# Robot_Psoc.net
KiCad netlist of a schematic drawn in EAGLE
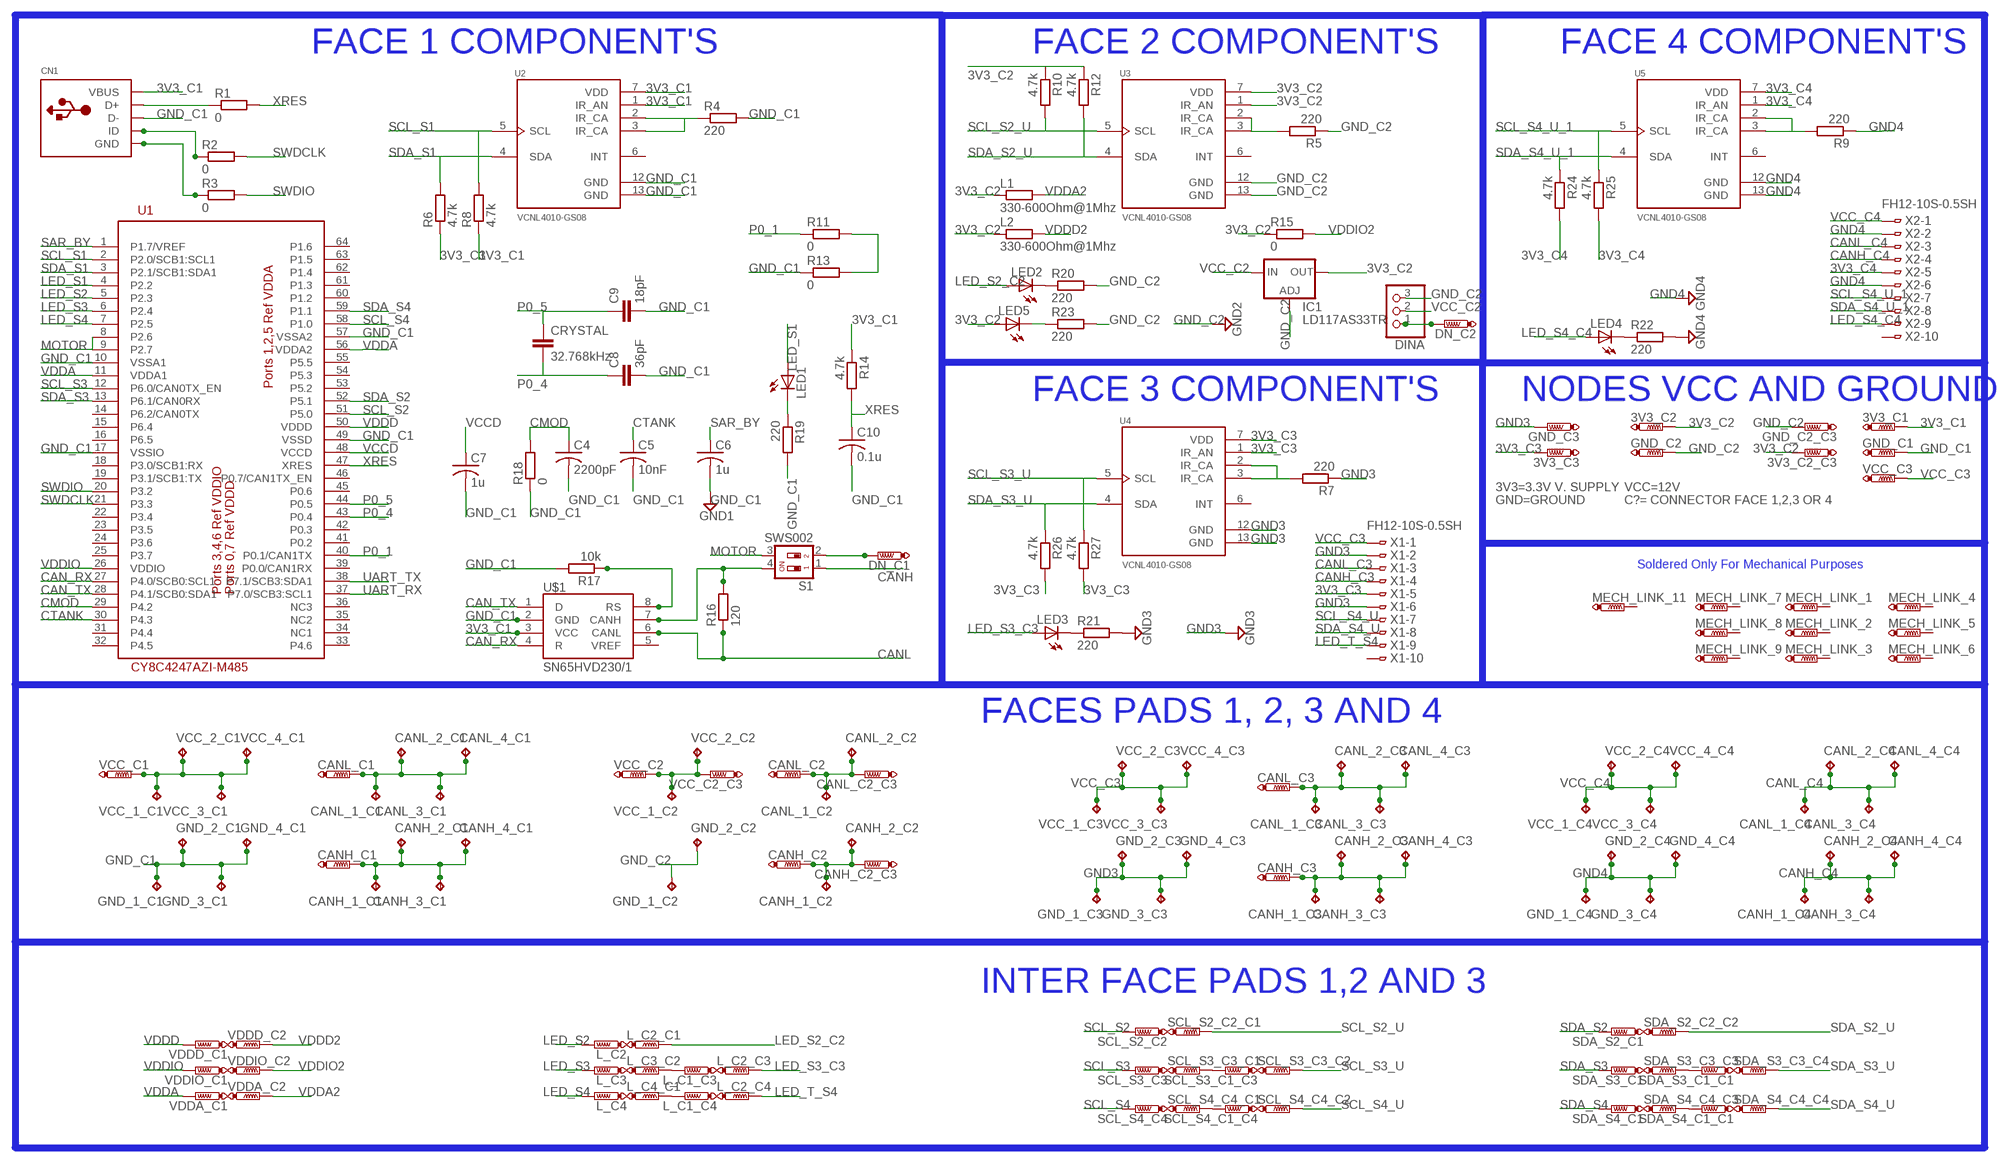
[diagram p0: schematic, sheet 1]

(export (version "E")
  (design (tool "Eeschema 10.0.6"))
  (components
    (comp (ref "3V3_C1")
      (value "PTR1TP11R")
      (footprint "eagle-import:TP11R")
      (libsource (lib "eagle-import") (part "PTR1TP11R"))
    )
    (comp (ref "3V3_C2")
      (value "PTR1TP11R")
      (footprint "eagle-import:TP11R")
      (libsource (lib "eagle-import") (part "PTR1TP11R"))
    )
    (comp (ref "3V3_C2_C3")
      (value "PTR1TP11R")
      (footprint "eagle-import:TP11R")
      (libsource (lib "eagle-import") (part "PTR1TP11R"))
    )
    (comp (ref "3V3_C3")
      (value "PTR1TP11R")
      (footprint "eagle-import:TP11R")
      (libsource (lib "eagle-import") (part "PTR1TP11R"))
    )
    (comp (ref "C4")
      (value "2200pF")
      (footprint "eagle-import:C0805")
      (libsource (lib "eagle-import") (part "C-USC0805"))
    )
    (comp (ref "C5")
      (value "10nF")
      (footprint "eagle-import:C0805")
      (libsource (lib "eagle-import") (part "C-USC0805"))
    )
    (comp (ref "C6")
      (value "1u")
      (footprint "eagle-import:C0805")
      (libsource (lib "eagle-import") (part "C-USC0805"))
    )
    (comp (ref "C7")
      (value "1u")
      (footprint "eagle-import:C0805")
      (libsource (lib "eagle-import") (part "C-USC0805"))
    )
    (comp (ref "C8")
      (value "36pF")
      (footprint "eagle-import:C0805")
      (libsource (lib "eagle-import") (part "C-EUC0805"))
    )
    (comp (ref "C9")
      (value "18pF")
      (footprint "eagle-import:C0805")
      (libsource (lib "eagle-import") (part "C-EUC0805"))
    )
    (comp (ref "C10")
      (value "0.1u")
      (footprint "eagle-import:C0805")
      (libsource (lib "eagle-import") (part "C-USC0805"))
    )
    (comp (ref "CANH_1_C1")
      (value "TPB2,54")
      (footprint "eagle-import:B2,54")
      (libsource (lib "eagle-import") (part "TPB2,54"))
    )
    (comp (ref "CANH_1_C2")
      (value "TPB2,54")
      (footprint "eagle-import:B2,54")
      (libsource (lib "eagle-import") (part "TPB2,54"))
    )
    (comp (ref "CANH_1_C3")
      (value "TPB2,54")
      (footprint "eagle-import:B2,54")
      (libsource (lib "eagle-import") (part "TPB2,54"))
    )
    (comp (ref "CANH_1_C4")
      (value "TPB2,54")
      (footprint "eagle-import:B2,54")
      (libsource (lib "eagle-import") (part "TPB2,54"))
    )
    (comp (ref "CANH_2_C1")
      (value "TPB2,54")
      (footprint "eagle-import:B2,54")
      (libsource (lib "eagle-import") (part "TPB2,54"))
    )
    (comp (ref "CANH_2_C2")
      (value "TPB2,54")
      (footprint "eagle-import:B2,54")
      (libsource (lib "eagle-import") (part "TPB2,54"))
    )
    (comp (ref "CANH_2_C3")
      (value "TPB2,54")
      (footprint "eagle-import:B2,54")
      (libsource (lib "eagle-import") (part "TPB2,54"))
    )
    (comp (ref "CANH_2_C4")
      (value "TPB2,54")
      (footprint "eagle-import:B2,54")
      (libsource (lib "eagle-import") (part "TPB2,54"))
    )
    (comp (ref "CANH_3_C1")
      (value "TPB2,54")
      (footprint "eagle-import:B2,54")
      (libsource (lib "eagle-import") (part "TPB2,54"))
    )
    (comp (ref "CANH_3_C3")
      (value "TPB2,54")
      (footprint "eagle-import:B2,54")
      (libsource (lib "eagle-import") (part "TPB2,54"))
    )
    (comp (ref "CANH_3_C4")
      (value "TPB2,54")
      (footprint "eagle-import:B2,54")
      (libsource (lib "eagle-import") (part "TPB2,54"))
    )
    (comp (ref "CANH_4_C1")
      (value "TPB2,54")
      (footprint "eagle-import:B2,54")
      (libsource (lib "eagle-import") (part "TPB2,54"))
    )
    (comp (ref "CANH_4_C3")
      (value "TPB2,54")
      (footprint "eagle-import:B2,54")
      (libsource (lib "eagle-import") (part "TPB2,54"))
    )
    (comp (ref "CANH_4_C4")
      (value "TPB2,54")
      (footprint "eagle-import:B2,54")
      (libsource (lib "eagle-import") (part "TPB2,54"))
    )
    (comp (ref "CANH_C1")
      (value "PTR1TP11R")
      (footprint "eagle-import:TP11R")
      (libsource (lib "eagle-import") (part "PTR1TP11R"))
    )
    (comp (ref "CANH_C2")
      (value "PTR1TP11R")
      (footprint "eagle-import:TP11R")
      (libsource (lib "eagle-import") (part "PTR1TP11R"))
    )
    (comp (ref "CANH_C2_C3")
      (value "PTR1TP11R")
      (footprint "eagle-import:TP11R")
      (libsource (lib "eagle-import") (part "PTR1TP11R"))
    )
    (comp (ref "CANH_C3")
      (value "PTR1TP11R")
      (footprint "eagle-import:TP11R")
      (libsource (lib "eagle-import") (part "PTR1TP11R"))
    )
    (comp (ref "CANL_1_C1")
      (value "TPB2,54")
      (footprint "eagle-import:B2,54")
      (libsource (lib "eagle-import") (part "TPB2,54"))
    )
    (comp (ref "CANL_1_C2")
      (value "TPB2,54")
      (footprint "eagle-import:B2,54")
      (libsource (lib "eagle-import") (part "TPB2,54"))
    )
    (comp (ref "CANL_1_C3")
      (value "TPB2,54")
      (footprint "eagle-import:B2,54")
      (libsource (lib "eagle-import") (part "TPB2,54"))
    )
    (comp (ref "CANL_1_C4")
      (value "TPB2,54")
      (footprint "eagle-import:B2,54")
      (libsource (lib "eagle-import") (part "TPB2,54"))
    )
    (comp (ref "CANL_2_C1")
      (value "TPB2,54")
      (footprint "eagle-import:B2,54")
      (libsource (lib "eagle-import") (part "TPB2,54"))
    )
    (comp (ref "CANL_2_C2")
      (value "TPB2,54")
      (footprint "eagle-import:B2,54")
      (libsource (lib "eagle-import") (part "TPB2,54"))
    )
    (comp (ref "CANL_2_C3")
      (value "TPB2,54")
      (footprint "eagle-import:B2,54")
      (libsource (lib "eagle-import") (part "TPB2,54"))
    )
    (comp (ref "CANL_2_C4")
      (value "TPB2,54")
      (footprint "eagle-import:B2,54")
      (libsource (lib "eagle-import") (part "TPB2,54"))
    )
    (comp (ref "CANL_3_C1")
      (value "TPB2,54")
      (footprint "eagle-import:B2,54")
      (libsource (lib "eagle-import") (part "TPB2,54"))
    )
    (comp (ref "CANL_3_C3")
      (value "TPB2,54")
      (footprint "eagle-import:B2,54")
      (libsource (lib "eagle-import") (part "TPB2,54"))
    )
    (comp (ref "CANL_3_C4")
      (value "TPB2,54")
      (footprint "eagle-import:B2,54")
      (libsource (lib "eagle-import") (part "TPB2,54"))
    )
    (comp (ref "CANL_4_C1")
      (value "TPB2,54")
      (footprint "eagle-import:B2,54")
      (libsource (lib "eagle-import") (part "TPB2,54"))
    )
    (comp (ref "CANL_4_C3")
      (value "TPB2,54")
      (footprint "eagle-import:B2,54")
      (libsource (lib "eagle-import") (part "TPB2,54"))
    )
    (comp (ref "CANL_4_C4")
      (value "TPB2,54")
      (footprint "eagle-import:B2,54")
      (libsource (lib "eagle-import") (part "TPB2,54"))
    )
    (comp (ref "CANL_C1")
      (value "PTR1TP11R")
      (footprint "eagle-import:TP11R")
      (libsource (lib "eagle-import") (part "PTR1TP11R"))
    )
    (comp (ref "CANL_C2")
      (value "PTR1TP11R")
      (footprint "eagle-import:TP11R")
      (libsource (lib "eagle-import") (part "PTR1TP11R"))
    )
    (comp (ref "CANL_C2_C3")
      (value "PTR1TP11R")
      (footprint "eagle-import:TP11R")
      (libsource (lib "eagle-import") (part "PTR1TP11R"))
    )
    (comp (ref "CANL_C3")
      (value "PTR1TP11R")
      (footprint "eagle-import:TP11R")
      (libsource (lib "eagle-import") (part "PTR1TP11R"))
    )
    (comp (ref "CN1")
      (value "USBMINIB")
      (footprint "eagle-import:USB-MINIB")
      (libsource (lib "eagle-import") (part "USBMINIB"))
    )
    (comp (ref "CRYSTAL")
      (value "32.768kHz")
      (footprint "eagle-import:C0603")
      (libsource (lib "eagle-import") (part "C-EUC0603"))
    )
    (comp (ref "DINA")
      (value "PINHD-1X3")
      (footprint "eagle-import:1X03")
      (libsource (lib "eagle-import") (part "PINHD-1X3"))
    )
    (comp (ref "DN_C1")
      (value "PTR1TP11R")
      (footprint "eagle-import:TP11R")
      (libsource (lib "eagle-import") (part "PTR1TP11R"))
    )
    (comp (ref "DN_C2")
      (value "PTR1TP11R")
      (footprint "eagle-import:TP11R")
      (libsource (lib "eagle-import") (part "PTR1TP11R"))
    )
    (comp (ref "GND_1_C1")
      (value "TPB2,54")
      (footprint "eagle-import:B2,54")
      (libsource (lib "eagle-import") (part "TPB2,54"))
    )
    (comp (ref "GND_1_C2")
      (value "TPB2,54")
      (footprint "eagle-import:B2,54")
      (libsource (lib "eagle-import") (part "TPB2,54"))
    )
    (comp (ref "GND_1_C3")
      (value "TPB2,54")
      (footprint "eagle-import:B2,54")
      (libsource (lib "eagle-import") (part "TPB2,54"))
    )
    (comp (ref "GND_1_C4")
      (value "TPB2,54")
      (footprint "eagle-import:B2,54")
      (libsource (lib "eagle-import") (part "TPB2,54"))
    )
    (comp (ref "GND_2_C1")
      (value "TPB2,54")
      (footprint "eagle-import:B2,54")
      (libsource (lib "eagle-import") (part "TPB2,54"))
    )
    (comp (ref "GND_2_C2")
      (value "TPB2,54")
      (footprint "eagle-import:B2,54")
      (libsource (lib "eagle-import") (part "TPB2,54"))
    )
    (comp (ref "GND_2_C3")
      (value "TPB2,54")
      (footprint "eagle-import:B2,54")
      (libsource (lib "eagle-import") (part "TPB2,54"))
    )
    (comp (ref "GND_2_C4")
      (value "TPB2,54")
      (footprint "eagle-import:B2,54")
      (libsource (lib "eagle-import") (part "TPB2,54"))
    )
    (comp (ref "GND_3_C1")
      (value "TPB2,54")
      (footprint "eagle-import:B2,54")
      (libsource (lib "eagle-import") (part "TPB2,54"))
    )
    (comp (ref "GND_3_C3")
      (value "TPB2,54")
      (footprint "eagle-import:B2,54")
      (libsource (lib "eagle-import") (part "TPB2,54"))
    )
    (comp (ref "GND_3_C4")
      (value "TPB2,54")
      (footprint "eagle-import:B2,54")
      (libsource (lib "eagle-import") (part "TPB2,54"))
    )
    (comp (ref "GND_4_C1")
      (value "TPB2,54")
      (footprint "eagle-import:B2,54")
      (libsource (lib "eagle-import") (part "TPB2,54"))
    )
    (comp (ref "GND_4_C3")
      (value "TPB2,54")
      (footprint "eagle-import:B2,54")
      (libsource (lib "eagle-import") (part "TPB2,54"))
    )
    (comp (ref "GND_4_C4")
      (value "TPB2,54")
      (footprint "eagle-import:B2,54")
      (libsource (lib "eagle-import") (part "TPB2,54"))
    )
    (comp (ref "GND_C1")
      (value "PTR1TP11R")
      (footprint "eagle-import:TP11R")
      (libsource (lib "eagle-import") (part "PTR1TP11R"))
    )
    (comp (ref "GND_C2")
      (value "PTR1TP11R")
      (footprint "eagle-import:TP11R")
      (libsource (lib "eagle-import") (part "PTR1TP11R"))
    )
    (comp (ref "GND_C2_C3")
      (value "PTR1TP11R")
      (footprint "eagle-import:TP11R")
      (libsource (lib "eagle-import") (part "PTR1TP11R"))
    )
    (comp (ref "GND_C3")
      (value "PTR1TP11R")
      (footprint "eagle-import:TP11R")
      (libsource (lib "eagle-import") (part "PTR1TP11R"))
    )
    (comp (ref "IC1")
      (value "LD117AS33TR")
      (footprint "eagle-import:SOT223")
      (libsource (lib "eagle-import") (part "LD117A?S33TR"))
    )
    (comp (ref "L1")
      (value "330-600Ohm@1Mhz")
      (footprint "eagle-import:R0805")
      (libsource (lib "eagle-import") (part "R-EU_R0805"))
    )
    (comp (ref "L2")
      (value "330-600Ohm@1Mhz")
      (footprint "eagle-import:R0805")
      (libsource (lib "eagle-import") (part "R-EU_R0805"))
    )
    (comp (ref "LED1")
      (value "LEDCHIPLED_0805")
      (footprint "eagle-import:CHIPLED_0805")
      (libsource (lib "eagle-import") (part "LEDCHIPLED_0805"))
    )
    (comp (ref "LED2")
      (value "LEDCHIPLED_0805")
      (footprint "eagle-import:CHIPLED_0805")
      (libsource (lib "eagle-import") (part "LEDCHIPLED_0805"))
    )
    (comp (ref "LED3")
      (value "LEDCHIPLED_0805")
      (footprint "eagle-import:CHIPLED_0805")
      (libsource (lib "eagle-import") (part "LEDCHIPLED_0805"))
    )
    (comp (ref "LED4")
      (value "LEDCHIPLED_0805")
      (footprint "eagle-import:CHIPLED_0805")
      (libsource (lib "eagle-import") (part "LEDCHIPLED_0805"))
    )
    (comp (ref "LED5")
      (value "LEDCHIPLED_0805")
      (footprint "eagle-import:CHIPLED_0805")
      (libsource (lib "eagle-import") (part "LEDCHIPLED_0805"))
    )
    (comp (ref "L_C1_C3")
      (value "PTR1TP11R")
      (footprint "eagle-import:TP11R")
      (libsource (lib "eagle-import") (part "PTR1TP11R"))
    )
    (comp (ref "L_C1_C4")
      (value "PTR1TP11R")
      (footprint "eagle-import:TP11R")
      (libsource (lib "eagle-import") (part "PTR1TP11R"))
    )
    (comp (ref "L_C2")
      (value "PTR1TP11R")
      (footprint "eagle-import:TP11R")
      (libsource (lib "eagle-import") (part "PTR1TP11R"))
    )
    (comp (ref "L_C2_C1")
      (value "PTR1TP11R")
      (footprint "eagle-import:TP11R")
      (libsource (lib "eagle-import") (part "PTR1TP11R"))
    )
    (comp (ref "L_C2_C3")
      (value "PTR1TP11R")
      (footprint "eagle-import:TP11R")
      (libsource (lib "eagle-import") (part "PTR1TP11R"))
    )
    (comp (ref "L_C2_C4")
      (value "PTR1TP11R")
      (footprint "eagle-import:TP11R")
      (libsource (lib "eagle-import") (part "PTR1TP11R"))
    )
    (comp (ref "L_C3")
      (value "PTR1TP11R")
      (footprint "eagle-import:TP11R")
      (libsource (lib "eagle-import") (part "PTR1TP11R"))
    )
    (comp (ref "L_C3_C2")
      (value "PTR1TP11R")
      (footprint "eagle-import:TP11R")
      (libsource (lib "eagle-import") (part "PTR1TP11R"))
    )
    (comp (ref "L_C4")
      (value "PTR1TP11R")
      (footprint "eagle-import:TP11R")
      (libsource (lib "eagle-import") (part "PTR1TP11R"))
    )
    (comp (ref "L_C4_C1")
      (value "PTR1TP11R")
      (footprint "eagle-import:TP11R")
      (libsource (lib "eagle-import") (part "PTR1TP11R"))
    )
    (comp (ref "MECH_LINK_1")
      (value "PTR1TP11R")
      (footprint "eagle-import:TP11R")
      (libsource (lib "eagle-import") (part "PTR1TP11R"))
    )
    (comp (ref "MECH_LINK_2")
      (value "PTR1TP11R")
      (footprint "eagle-import:TP11R")
      (libsource (lib "eagle-import") (part "PTR1TP11R"))
    )
    (comp (ref "MECH_LINK_3")
      (value "PTR1TP11R")
      (footprint "eagle-import:TP11R")
      (libsource (lib "eagle-import") (part "PTR1TP11R"))
    )
    (comp (ref "MECH_LINK_4")
      (value "PTR1TP11R")
      (footprint "eagle-import:TP11R")
      (libsource (lib "eagle-import") (part "PTR1TP11R"))
    )
    (comp (ref "MECH_LINK_5")
      (value "PTR1TP11R")
      (footprint "eagle-import:TP11R")
      (libsource (lib "eagle-import") (part "PTR1TP11R"))
    )
    (comp (ref "MECH_LINK_6")
      (value "PTR1TP11R")
      (footprint "eagle-import:TP11R")
      (libsource (lib "eagle-import") (part "PTR1TP11R"))
    )
    (comp (ref "MECH_LINK_7")
      (value "PTR1TP11R")
      (footprint "eagle-import:TP11R")
      (libsource (lib "eagle-import") (part "PTR1TP11R"))
    )
    (comp (ref "MECH_LINK_8")
      (value "PTR1TP11R")
      (footprint "eagle-import:TP11R")
      (libsource (lib "eagle-import") (part "PTR1TP11R"))
    )
    (comp (ref "MECH_LINK_9")
      (value "PTR1TP11R")
      (footprint "eagle-import:TP11R")
      (libsource (lib "eagle-import") (part "PTR1TP11R"))
    )
    (comp (ref "MECH_LINK_11")
      (value "PTR1TP11R")
      (footprint "eagle-import:TP11R")
      (libsource (lib "eagle-import") (part "PTR1TP11R"))
    )
    (comp (ref "R1")
      (value "0")
      (footprint "eagle-import:R0805")
      (libsource (lib "eagle-import") (part "R-EU_R0805"))
    )
    (comp (ref "R2")
      (value "0")
      (footprint "eagle-import:R0805")
      (libsource (lib "eagle-import") (part "R-EU_R0805"))
    )
    (comp (ref "R3")
      (value "0")
      (footprint "eagle-import:R0805")
      (libsource (lib "eagle-import") (part "R-EU_R0805"))
    )
    (comp (ref "R4")
      (value "220")
      (footprint "eagle-import:R0805")
      (libsource (lib "eagle-import") (part "R-EU_R0805"))
    )
    (comp (ref "R5")
      (value "220")
      (footprint "eagle-import:R0805")
      (libsource (lib "eagle-import") (part "R-EU_R0805"))
    )
    (comp (ref "R6")
      (value "4.7k")
      (footprint "eagle-import:R0805")
      (libsource (lib "eagle-import") (part "R-EU_R0805"))
    )
    (comp (ref "R7")
      (value "220")
      (footprint "eagle-import:R0805")
      (libsource (lib "eagle-import") (part "R-EU_R0805"))
    )
    (comp (ref "R8")
      (value "4.7k")
      (footprint "eagle-import:R0805")
      (libsource (lib "eagle-import") (part "R-EU_R0805"))
    )
    (comp (ref "R9")
      (value "220")
      (footprint "eagle-import:R0805")
      (libsource (lib "eagle-import") (part "R-EU_R0805"))
    )
    (comp (ref "R10")
      (value "4.7k")
      (footprint "eagle-import:R0805")
      (libsource (lib "eagle-import") (part "R-EU_R0805"))
    )
    (comp (ref "R11")
      (value "0")
      (footprint "eagle-import:R0805")
      (libsource (lib "eagle-import") (part "R-EU_R0805"))
    )
    (comp (ref "R12")
      (value "4.7k")
      (footprint "eagle-import:R0805")
      (libsource (lib "eagle-import") (part "R-EU_R0805"))
    )
    (comp (ref "R13")
      (value "0")
      (footprint "eagle-import:R0805")
      (libsource (lib "eagle-import") (part "R-EU_R0805"))
    )
    (comp (ref "R14")
      (value "4.7k")
      (footprint "eagle-import:R0805")
      (libsource (lib "eagle-import") (part "R-EU_R0805"))
    )
    (comp (ref "R15")
      (value "0")
      (footprint "eagle-import:R0805")
      (libsource (lib "eagle-import") (part "R-EU_R0805"))
    )
    (comp (ref "R16")
      (value "120")
      (footprint "eagle-import:R0805")
      (libsource (lib "eagle-import") (part "R-EU_R0805"))
    )
    (comp (ref "R17")
      (value "10k")
      (footprint "eagle-import:R0805")
      (libsource (lib "eagle-import") (part "R-EU_R0805"))
    )
    (comp (ref "R18")
      (value "0")
      (footprint "eagle-import:R0805")
      (libsource (lib "eagle-import") (part "R-EU_R0805"))
    )
    (comp (ref "R19")
      (value "220")
      (footprint "eagle-import:R0805")
      (libsource (lib "eagle-import") (part "R-EU_R0805"))
    )
    (comp (ref "R20")
      (value "220")
      (footprint "eagle-import:R0805")
      (libsource (lib "eagle-import") (part "R-EU_R0805"))
    )
    (comp (ref "R21")
      (value "220")
      (footprint "eagle-import:R0805")
      (libsource (lib "eagle-import") (part "R-EU_R0805"))
    )
    (comp (ref "R22")
      (value "220")
      (footprint "eagle-import:R0805")
      (libsource (lib "eagle-import") (part "R-EU_R0805"))
    )
    (comp (ref "R23")
      (value "220")
      (footprint "eagle-import:R0805")
      (libsource (lib "eagle-import") (part "R-EU_R0805"))
    )
    (comp (ref "R24")
      (value "4.7k")
      (footprint "eagle-import:R0805")
      (libsource (lib "eagle-import") (part "R-EU_R0805"))
    )
    (comp (ref "R25")
      (value "4.7k")
      (footprint "eagle-import:R0805")
      (libsource (lib "eagle-import") (part "R-EU_R0805"))
    )
    (comp (ref "R26")
      (value "4.7k")
      (footprint "eagle-import:R0805")
      (libsource (lib "eagle-import") (part "R-EU_R0805"))
    )
    (comp (ref "R27")
      (value "4.7k")
      (footprint "eagle-import:R0805")
      (libsource (lib "eagle-import") (part "R-EU_R0805"))
    )
    (comp (ref "S1")
      (value "SWS002")
      (footprint "eagle-import:SMS-002")
      (libsource (lib "eagle-import") (part "SWS002"))
    )
    (comp (ref "SCL_S2_C2")
      (value "PTR1TP11R")
      (footprint "eagle-import:TP11R")
      (libsource (lib "eagle-import") (part "PTR1TP11R"))
    )
    (comp (ref "SCL_S2_C2_C1")
      (value "PTR1TP11R")
      (footprint "eagle-import:TP11R")
      (libsource (lib "eagle-import") (part "PTR1TP11R"))
    )
    (comp (ref "SCL_S3_C1_C3")
      (value "PTR1TP11R")
      (footprint "eagle-import:TP11R")
      (libsource (lib "eagle-import") (part "PTR1TP11R"))
    )
    (comp (ref "SCL_S3_C3")
      (value "PTR1TP11R")
      (footprint "eagle-import:TP11R")
      (libsource (lib "eagle-import") (part "PTR1TP11R"))
    )
    (comp (ref "SCL_S3_C3_C1")
      (value "PTR1TP11R")
      (footprint "eagle-import:TP11R")
      (libsource (lib "eagle-import") (part "PTR1TP11R"))
    )
    (comp (ref "SCL_S3_C3_C2")
      (value "PTR1TP11R")
      (footprint "eagle-import:TP11R")
      (libsource (lib "eagle-import") (part "PTR1TP11R"))
    )
    (comp (ref "SCL_S4_C1_C4")
      (value "PTR1TP11R")
      (footprint "eagle-import:TP11R")
      (libsource (lib "eagle-import") (part "PTR1TP11R"))
    )
    (comp (ref "SCL_S4_C4")
      (value "PTR1TP11R")
      (footprint "eagle-import:TP11R")
      (libsource (lib "eagle-import") (part "PTR1TP11R"))
    )
    (comp (ref "SCL_S4_C4_C1")
      (value "PTR1TP11R")
      (footprint "eagle-import:TP11R")
      (libsource (lib "eagle-import") (part "PTR1TP11R"))
    )
    (comp (ref "SCL_S4_C4_C2")
      (value "PTR1TP11R")
      (footprint "eagle-import:TP11R")
      (libsource (lib "eagle-import") (part "PTR1TP11R"))
    )
    (comp (ref "SDA_S2_C1")
      (value "PTR1TP11R")
      (footprint "eagle-import:TP11R")
      (libsource (lib "eagle-import") (part "PTR1TP11R"))
    )
    (comp (ref "SDA_S2_C2_C2")
      (value "PTR1TP11R")
      (footprint "eagle-import:TP11R")
      (libsource (lib "eagle-import") (part "PTR1TP11R"))
    )
    (comp (ref "SDA_S3_C1")
      (value "PTR1TP11R")
      (footprint "eagle-import:TP11R")
      (libsource (lib "eagle-import") (part "PTR1TP11R"))
    )
    (comp (ref "SDA_S3_C1_C1")
      (value "PTR1TP11R")
      (footprint "eagle-import:TP11R")
      (libsource (lib "eagle-import") (part "PTR1TP11R"))
    )
    (comp (ref "SDA_S3_C3_C3")
      (value "PTR1TP11R")
      (footprint "eagle-import:TP11R")
      (libsource (lib "eagle-import") (part "PTR1TP11R"))
    )
    (comp (ref "SDA_S3_C3_C4")
      (value "PTR1TP11R")
      (footprint "eagle-import:TP11R")
      (libsource (lib "eagle-import") (part "PTR1TP11R"))
    )
    (comp (ref "SDA_S4_C1")
      (value "PTR1TP11R")
      (footprint "eagle-import:TP11R")
      (libsource (lib "eagle-import") (part "PTR1TP11R"))
    )
    (comp (ref "SDA_S4_C1_C1")
      (value "PTR1TP11R")
      (footprint "eagle-import:TP11R")
      (libsource (lib "eagle-import") (part "PTR1TP11R"))
    )
    (comp (ref "SDA_S4_C4_C3")
      (value "PTR1TP11R")
      (footprint "eagle-import:TP11R")
      (libsource (lib "eagle-import") (part "PTR1TP11R"))
    )
    (comp (ref "SDA_S4_C4_C4")
      (value "PTR1TP11R")
      (footprint "eagle-import:TP11R")
      (libsource (lib "eagle-import") (part "PTR1TP11R"))
    )
    (comp (ref "U$1")
      (value "SN65HVD230/1")
      (footprint "eagle-import:SO8")
      (libsource (lib "eagle-import") (part "SN65HVD230/1"))
    )
    (comp (ref "U1")
      (value "CY8C4247AZI-M485")
      (footprint "eagle-import:TQFP64-10X10")
      (libsource (lib "eagle-import") (part "CY8C4247AZI-M485"))
    )
    (comp (ref "U2")
      (value "VCNL4010-GS08")
      (footprint "eagle-import:XDCR_VCNL4010-GS08")
      (libsource (lib "eagle-import") (part "VCNL4010-GS08"))
    )
    (comp (ref "U3")
      (value "VCNL4010-GS08")
      (footprint "eagle-import:XDCR_VCNL4010-GS08")
      (libsource (lib "eagle-import") (part "VCNL4010-GS08"))
    )
    (comp (ref "U4")
      (value "VCNL4010-GS08")
      (footprint "eagle-import:XDCR_VCNL4010-GS08")
      (libsource (lib "eagle-import") (part "VCNL4010-GS08"))
    )
    (comp (ref "U5")
      (value "VCNL4010-GS08")
      (footprint "eagle-import:XDCR_VCNL4010-GS08")
      (libsource (lib "eagle-import") (part "VCNL4010-GS08"))
    )
    (comp (ref "VCC_1_C1")
      (value "TPB2,54")
      (footprint "eagle-import:B2,54")
      (libsource (lib "eagle-import") (part "TPB2,54"))
    )
    (comp (ref "VCC_1_C2")
      (value "TPB2,54")
      (footprint "eagle-import:B2,54")
      (libsource (lib "eagle-import") (part "TPB2,54"))
    )
    (comp (ref "VCC_1_C3")
      (value "TPB2,54")
      (footprint "eagle-import:B2,54")
      (libsource (lib "eagle-import") (part "TPB2,54"))
    )
    (comp (ref "VCC_1_C4")
      (value "TPB2,54")
      (footprint "eagle-import:B2,54")
      (libsource (lib "eagle-import") (part "TPB2,54"))
    )
    (comp (ref "VCC_2_C1")
      (value "TPB2,54")
      (footprint "eagle-import:B2,54")
      (libsource (lib "eagle-import") (part "TPB2,54"))
    )
    (comp (ref "VCC_2_C2")
      (value "TPB2,54")
      (footprint "eagle-import:B2,54")
      (libsource (lib "eagle-import") (part "TPB2,54"))
    )
    (comp (ref "VCC_2_C3")
      (value "TPB2,54")
      (footprint "eagle-import:B2,54")
      (libsource (lib "eagle-import") (part "TPB2,54"))
    )
    (comp (ref "VCC_2_C4")
      (value "TPB2,54")
      (footprint "eagle-import:B2,54")
      (libsource (lib "eagle-import") (part "TPB2,54"))
    )
    (comp (ref "VCC_3_C1")
      (value "TPB2,54")
      (footprint "eagle-import:B2,54")
      (libsource (lib "eagle-import") (part "TPB2,54"))
    )
    (comp (ref "VCC_3_C3")
      (value "TPB2,54")
      (footprint "eagle-import:B2,54")
      (libsource (lib "eagle-import") (part "TPB2,54"))
    )
    (comp (ref "VCC_3_C4")
      (value "TPB2,54")
      (footprint "eagle-import:B2,54")
      (libsource (lib "eagle-import") (part "TPB2,54"))
    )
    (comp (ref "VCC_4_C1")
      (value "TPB2,54")
      (footprint "eagle-import:B2,54")
      (libsource (lib "eagle-import") (part "TPB2,54"))
    )
    (comp (ref "VCC_4_C3")
      (value "TPB2,54")
      (footprint "eagle-import:B2,54")
      (libsource (lib "eagle-import") (part "TPB2,54"))
    )
    (comp (ref "VCC_4_C4")
      (value "TPB2,54")
      (footprint "eagle-import:B2,54")
      (libsource (lib "eagle-import") (part "TPB2,54"))
    )
    (comp (ref "VCC_C1")
      (value "PTR1TP11R")
      (footprint "eagle-import:TP11R")
      (libsource (lib "eagle-import") (part "PTR1TP11R"))
    )
    (comp (ref "VCC_C2")
      (value "PTR1TP11R")
      (footprint "eagle-import:TP11R")
      (libsource (lib "eagle-import") (part "PTR1TP11R"))
    )
    (comp (ref "VCC_C2_C3")
      (value "PTR1TP11R")
      (footprint "eagle-import:TP11R")
      (libsource (lib "eagle-import") (part "PTR1TP11R"))
    )
    (comp (ref "VCC_C3")
      (value "PTR1TP11R")
      (footprint "eagle-import:TP11R")
      (libsource (lib "eagle-import") (part "PTR1TP11R"))
    )
    (comp (ref "VDDA_C1")
      (value "PTR1TP11R")
      (footprint "eagle-import:TP11R")
      (libsource (lib "eagle-import") (part "PTR1TP11R"))
    )
    (comp (ref "VDDA_C2")
      (value "PTR1TP11R")
      (footprint "eagle-import:TP11R")
      (libsource (lib "eagle-import") (part "PTR1TP11R"))
    )
    (comp (ref "VDDD_C1")
      (value "PTR1TP11R")
      (footprint "eagle-import:TP11R")
      (libsource (lib "eagle-import") (part "PTR1TP11R"))
    )
    (comp (ref "VDDD_C2")
      (value "PTR1TP11R")
      (footprint "eagle-import:TP11R")
      (libsource (lib "eagle-import") (part "PTR1TP11R"))
    )
    (comp (ref "VDDIO_C1")
      (value "PTR1TP11R")
      (footprint "eagle-import:TP11R")
      (libsource (lib "eagle-import") (part "PTR1TP11R"))
    )
    (comp (ref "VDDIO_C2")
      (value "PTR1TP11R")
      (footprint "eagle-import:TP11R")
      (libsource (lib "eagle-import") (part "PTR1TP11R"))
    )
    (comp (ref "X1")
      (value "FH12-10S-0.5SH")
      (footprint "eagle-import:FH12-10S-0.5SH")
      (fields (field (name "MPN") "FH12-10S-0.5SH(55)"))
      (libsource (lib "eagle-import") (part "FH12-10S-0.5SH"))
    )
    (comp (ref "X2")
      (value "FH12-10S-0.5SH")
      (footprint "eagle-import:FH12-10S-0.5SH")
      (fields (field (name "MPN") "FH12-10S-0.5SH(55)"))
      (libsource (lib "eagle-import") (part "FH12-10S-0.5SH"))
    )
  )
  (nets
    (net (code "1") (name "/3V3_C1") (class "Default")
      (node (ref "3V3_C1") (pin "TP") (pinfunction "TP_TP") (pintype "input"))
      (node (ref "CN1") (pin "VBUS") (pinfunction "VBUS_VBUS") (pintype "power_in"))
      (node (ref "R14") (pin "1") (pinfunction "1_1") (pintype "passive"))
      (node (ref "R6") (pin "1") (pinfunction "1_1") (pintype "passive"))
      (node (ref "R8") (pin "1") (pinfunction "1_1") (pintype "passive"))
      (node (ref "U$1") (pin "3") (pinfunction "VCC_3") (pintype "power_in"))
      (node (ref "U2") (pin "1") (pinfunction "IR_AN_1") (pintype "power_in"))
      (node (ref "U2") (pin "7") (pinfunction "VDD_7") (pintype "power_in"))
    )
    (net (code "2") (name "/3V3_C2") (class "Default")
      (node (ref "3V3_C2") (pin "TP") (pinfunction "TP_TP") (pintype "input"))
      (node (ref "3V3_C2_C3") (pin "TP") (pinfunction "TP_TP") (pintype "input"))
      (node (ref "IC1") (pin "4") (pinfunction "OUT_4") (pintype "passive"))
      (node (ref "L1") (pin "1") (pinfunction "1_1") (pintype "passive"))
      (node (ref "L2") (pin "1") (pinfunction "1_1") (pintype "passive"))
      (node (ref "LED5") (pin "A") (pinfunction "A_A") (pintype "passive"))
      (node (ref "R10") (pin "1") (pinfunction "1_1") (pintype "passive"))
      (node (ref "R12") (pin "1") (pinfunction "1_1") (pintype "passive"))
      (node (ref "R15") (pin "1") (pinfunction "1_1") (pintype "passive"))
      (node (ref "U3") (pin "1") (pinfunction "IR_AN_1") (pintype "power_in"))
      (node (ref "U3") (pin "7") (pinfunction "VDD_7") (pintype "power_in"))
    )
    (net (code "3") (name "/3V3_C3") (class "Default")
      (node (ref "3V3_C3") (pin "TP") (pinfunction "TP_TP") (pintype "input"))
      (node (ref "R26") (pin "2") (pinfunction "2_2") (pintype "passive"))
      (node (ref "R27") (pin "2") (pinfunction "2_2") (pintype "passive"))
      (node (ref "U4") (pin "1") (pinfunction "IR_AN_1") (pintype "power_in"))
      (node (ref "U4") (pin "7") (pinfunction "VDD_7") (pintype "power_in"))
      (node (ref "X1") (pin "5") (pinfunction "1_5") (pintype "passive"))
    )
    (net (code "4") (name "/3V3_C4") (class "Default")
      (node (ref "R24") (pin "2") (pinfunction "2_2") (pintype "passive"))
      (node (ref "R25") (pin "2") (pinfunction "2_2") (pintype "passive"))
      (node (ref "U5") (pin "1") (pinfunction "IR_AN_1") (pintype "power_in"))
      (node (ref "U5") (pin "7") (pinfunction "VDD_7") (pintype "power_in"))
      (node (ref "X2") (pin "5") (pinfunction "1_5") (pintype "passive"))
    )
    (net (code "5") (name "/CANH") (class "Default")
      (node (ref "CANH_1_C1") (pin "TP") (pinfunction "TP_TP") (pintype "input"))
      (node (ref "CANH_2_C1") (pin "TP") (pinfunction "TP_TP") (pintype "input"))
      (node (ref "CANH_3_C1") (pin "TP") (pinfunction "TP_TP") (pintype "input"))
      (node (ref "CANH_4_C1") (pin "TP") (pinfunction "TP_TP") (pintype "input"))
      (node (ref "CANH_C1") (pin "TP") (pinfunction "TP_TP") (pintype "input"))
      (node (ref "S1") (pin "1") (pinfunction "1_1") (pintype "passive"))
    )
    (net (code "6") (name "/CANH_C3") (class "Default")
      (node (ref "CANH_1_C3") (pin "TP") (pinfunction "TP_TP") (pintype "input"))
      (node (ref "CANH_2_C3") (pin "TP") (pinfunction "TP_TP") (pintype "input"))
      (node (ref "CANH_3_C3") (pin "TP") (pinfunction "TP_TP") (pintype "input"))
      (node (ref "CANH_4_C3") (pin "TP") (pinfunction "TP_TP") (pintype "input"))
      (node (ref "CANH_C3") (pin "TP") (pinfunction "TP_TP") (pintype "input"))
      (node (ref "X1") (pin "4") (pinfunction "1_4") (pintype "passive"))
    )
    (net (code "7") (name "/CANH_C4") (class "Default")
      (node (ref "CANH_1_C4") (pin "TP") (pinfunction "TP_TP") (pintype "input"))
      (node (ref "CANH_2_C4") (pin "TP") (pinfunction "TP_TP") (pintype "input"))
      (node (ref "CANH_3_C4") (pin "TP") (pinfunction "TP_TP") (pintype "input"))
      (node (ref "CANH_4_C4") (pin "TP") (pinfunction "TP_TP") (pintype "input"))
      (node (ref "X2") (pin "4") (pinfunction "1_4") (pintype "passive"))
    )
    (net (code "8") (name "/CANL") (class "Default")
      (node (ref "CANL_1_C1") (pin "TP") (pinfunction "TP_TP") (pintype "input"))
      (node (ref "CANL_2_C1") (pin "TP") (pinfunction "TP_TP") (pintype "input"))
      (node (ref "CANL_3_C1") (pin "TP") (pinfunction "TP_TP") (pintype "input"))
      (node (ref "CANL_4_C1") (pin "TP") (pinfunction "TP_TP") (pintype "input"))
      (node (ref "CANL_C1") (pin "TP") (pinfunction "TP_TP") (pintype "input"))
      (node (ref "R16") (pin "1") (pinfunction "1_1") (pintype "passive"))
      (node (ref "U$1") (pin "6") (pinfunction "CANL_6") (pintype "bidirectional"))
    )
    (net (code "9") (name "/CANL_C3") (class "Default")
      (node (ref "CANL_1_C3") (pin "TP") (pinfunction "TP_TP") (pintype "input"))
      (node (ref "CANL_2_C3") (pin "TP") (pinfunction "TP_TP") (pintype "input"))
      (node (ref "CANL_3_C3") (pin "TP") (pinfunction "TP_TP") (pintype "input"))
      (node (ref "CANL_4_C3") (pin "TP") (pinfunction "TP_TP") (pintype "input"))
      (node (ref "CANL_C3") (pin "TP") (pinfunction "TP_TP") (pintype "input"))
      (node (ref "X1") (pin "3") (pinfunction "1_3") (pintype "passive"))
    )
    (net (code "10") (name "/CANL_C4") (class "Default")
      (node (ref "CANL_1_C4") (pin "TP") (pinfunction "TP_TP") (pintype "input"))
      (node (ref "CANL_2_C4") (pin "TP") (pinfunction "TP_TP") (pintype "input"))
      (node (ref "CANL_3_C4") (pin "TP") (pinfunction "TP_TP") (pintype "input"))
      (node (ref "CANL_4_C4") (pin "TP") (pinfunction "TP_TP") (pintype "input"))
      (node (ref "X2") (pin "3") (pinfunction "1_3") (pintype "passive"))
    )
    (net (code "11") (name "/CAN_RX") (class "Default")
      (node (ref "U$1") (pin "4") (pinfunction "R_4") (pintype "bidirectional"))
      (node (ref "U1") (pin "27") (pinfunction "P4.0/SCB0:SCL1_27") (pintype "bidirectional"))
    )
    (net (code "12") (name "/CAN_TX") (class "Default")
      (node (ref "U$1") (pin "1") (pinfunction "D_1") (pintype "bidirectional"))
      (node (ref "U1") (pin "28") (pinfunction "P4.1/SCB0:SDA1_28") (pintype "bidirectional"))
    )
    (net (code "13") (name "/CMOD") (class "Default")
      (node (ref "C4") (pin "1") (pinfunction "1_1") (pintype "passive"))
      (node (ref "R18") (pin "2") (pinfunction "2_2") (pintype "passive"))
      (node (ref "U1") (pin "29") (pinfunction "P4.2_29") (pintype "bidirectional"))
    )
    (net (code "14") (name "/CTANK") (class "Default")
      (node (ref "C5") (pin "1") (pinfunction "1_1") (pintype "passive"))
      (node (ref "U1") (pin "30") (pinfunction "P4.3_30") (pintype "bidirectional"))
    )
    (net (code "15") (name "/LED_S1") (class "Default")
      (node (ref "LED1") (pin "A") (pinfunction "A_A") (pintype "passive"))
      (node (ref "U1") (pin "4") (pinfunction "P2.2_4") (pintype "bidirectional"))
    )
    (net (code "16") (name "/LED_S2") (class "Default")
      (node (ref "L_C2") (pin "TP") (pinfunction "TP_TP") (pintype "input"))
      (node (ref "U1") (pin "5") (pinfunction "P2.3_5") (pintype "bidirectional"))
    )
    (net (code "17") (name "/LED_S2_C2") (class "Default")
      (node (ref "LED2") (pin "A") (pinfunction "A_A") (pintype "passive"))
      (node (ref "L_C2_C1") (pin "TP") (pinfunction "TP_TP") (pintype "input"))
    )
    (net (code "18") (name "/LED_S3") (class "Default")
      (node (ref "L_C3") (pin "TP") (pinfunction "TP_TP") (pintype "input"))
      (node (ref "U1") (pin "6") (pinfunction "P2.4_6") (pintype "bidirectional"))
    )
    (net (code "19") (name "/LED_S3_C3") (class "Default")
      (node (ref "LED3") (pin "A") (pinfunction "A_A") (pintype "passive"))
      (node (ref "L_C2_C3") (pin "TP") (pinfunction "TP_TP") (pintype "input"))
    )
    (net (code "20") (name "/LED_S4") (class "Default")
      (node (ref "L_C4") (pin "TP") (pinfunction "TP_TP") (pintype "input"))
      (node (ref "U1") (pin "7") (pinfunction "P2.5_7") (pintype "bidirectional"))
    )
    (net (code "21") (name "/LED_S4_C4") (class "Default")
      (node (ref "LED4") (pin "A") (pinfunction "A_A") (pintype "passive"))
      (node (ref "X2") (pin "9") (pinfunction "1_9") (pintype "passive"))
    )
    (net (code "22") (name "/LED_T_S4") (class "Default")
      (node (ref "L_C2_C4") (pin "TP") (pinfunction "TP_TP") (pintype "input"))
      (node (ref "X1") (pin "9") (pinfunction "1_9") (pintype "passive"))
    )
    (net (code "23") (name "/MOTOR") (class "Default")
      (node (ref "S1") (pin "3") (pinfunction "3_3") (pintype "passive"))
      (node (ref "U1") (pin "8") (pinfunction "P2.6_8") (pintype "bidirectional"))
      (node (ref "U1") (pin "9") (pinfunction "P2.7_9") (pintype "bidirectional"))
    )
    (net (code "24") (name "/P0_1") (class "Default")
      (node (ref "R11") (pin "1") (pinfunction "1_1") (pintype "passive"))
      (node (ref "U1") (pin "40") (pinfunction "P0.1/CAN1TX_40") (pintype "bidirectional"))
    )
    (net (code "25") (name "/P0_4") (class "Default")
      (node (ref "C8") (pin "1") (pinfunction "1_1") (pintype "passive"))
      (node (ref "CRYSTAL") (pin "2") (pinfunction "2_2") (pintype "passive"))
      (node (ref "U1") (pin "43") (pinfunction "P0.4_43") (pintype "bidirectional"))
    )
    (net (code "26") (name "/P0_5") (class "Default")
      (node (ref "C9") (pin "1") (pinfunction "1_1") (pintype "passive"))
      (node (ref "CRYSTAL") (pin "1") (pinfunction "1_1") (pintype "passive"))
      (node (ref "U1") (pin "44") (pinfunction "P0.5_44") (pintype "bidirectional"))
    )
    (net (code "27") (name "/SAR_BY") (class "Default")
      (node (ref "C6") (pin "1") (pinfunction "1_1") (pintype "passive"))
      (node (ref "U1") (pin "1") (pinfunction "P1.7/VREF_1") (pintype "bidirectional"))
    )
    (net (code "28") (name "/SCL_S1") (class "Default")
      (node (ref "R8") (pin "2") (pinfunction "2_2") (pintype "passive"))
      (node (ref "U1") (pin "2") (pinfunction "P2.0/SCB1:SCL1_2") (pintype "bidirectional"))
      (node (ref "U2") (pin "5") (pinfunction "SCL_5") (pintype "input"))
    )
    (net (code "29") (name "/SCL_S2") (class "Default")
      (node (ref "SCL_S2_C2") (pin "TP") (pinfunction "TP_TP") (pintype "input"))
      (node (ref "U1") (pin "51") (pinfunction "P5.0_51") (pintype "bidirectional"))
    )
    (net (code "30") (name "/SCL_S2_U") (class "Default")
      (node (ref "R10") (pin "2") (pinfunction "2_2") (pintype "passive"))
      (node (ref "SCL_S2_C2_C1") (pin "TP") (pinfunction "TP_TP") (pintype "input"))
      (node (ref "U3") (pin "5") (pinfunction "SCL_5") (pintype "input"))
    )
    (net (code "31") (name "/SCL_S3") (class "Default")
      (node (ref "SCL_S3_C3") (pin "TP") (pinfunction "TP_TP") (pintype "input"))
      (node (ref "U1") (pin "12") (pinfunction "P6.0/CAN0TX_EN_12") (pintype "bidirectional"))
    )
    (net (code "32") (name "/SCL_S3_U") (class "Default")
      (node (ref "R27") (pin "1") (pinfunction "1_1") (pintype "passive"))
      (node (ref "SCL_S3_C3_C2") (pin "TP") (pinfunction "TP_TP") (pintype "input"))
      (node (ref "U4") (pin "5") (pinfunction "SCL_5") (pintype "input"))
    )
    (net (code "33") (name "/SCL_S4") (class "Default")
      (node (ref "SCL_S4_C4") (pin "TP") (pinfunction "TP_TP") (pintype "input"))
      (node (ref "U1") (pin "58") (pinfunction "P1.0_58") (pintype "bidirectional"))
    )
    (net (code "34") (name "/SCL_S4_U") (class "Default")
      (node (ref "SCL_S4_C4_C2") (pin "TP") (pinfunction "TP_TP") (pintype "input"))
      (node (ref "X1") (pin "7") (pinfunction "1_7") (pintype "passive"))
    )
    (net (code "35") (name "/SCL_S4_U_1") (class "Default")
      (node (ref "R25") (pin "1") (pinfunction "1_1") (pintype "passive"))
      (node (ref "U5") (pin "5") (pinfunction "SCL_5") (pintype "input"))
      (node (ref "X2") (pin "7") (pinfunction "1_7") (pintype "passive"))
    )
    (net (code "36") (name "/SDA_S1") (class "Default")
      (node (ref "R6") (pin "2") (pinfunction "2_2") (pintype "passive"))
      (node (ref "U1") (pin "3") (pinfunction "P2.1/SCB1:SDA1_3") (pintype "bidirectional"))
      (node (ref "U2") (pin "4") (pinfunction "SDA_4") (pintype "bidirectional"))
    )
    (net (code "37") (name "/SDA_S2") (class "Default")
      (node (ref "SDA_S2_C1") (pin "TP") (pinfunction "TP_TP") (pintype "input"))
      (node (ref "U1") (pin "52") (pinfunction "P5.1_52") (pintype "bidirectional"))
    )
    (net (code "38") (name "/SDA_S2_U") (class "Default")
      (node (ref "R12") (pin "2") (pinfunction "2_2") (pintype "passive"))
      (node (ref "SDA_S2_C2_C2") (pin "TP") (pinfunction "TP_TP") (pintype "input"))
      (node (ref "U3") (pin "4") (pinfunction "SDA_4") (pintype "bidirectional"))
    )
    (net (code "39") (name "/SDA_S3") (class "Default")
      (node (ref "SDA_S3_C1") (pin "TP") (pinfunction "TP_TP") (pintype "input"))
      (node (ref "U1") (pin "13") (pinfunction "P6.1/CAN0RX_13") (pintype "bidirectional"))
    )
    (net (code "40") (name "/SDA_S3_U") (class "Default")
      (node (ref "R26") (pin "1") (pinfunction "1_1") (pintype "passive"))
      (node (ref "SDA_S3_C3_C4") (pin "TP") (pinfunction "TP_TP") (pintype "input"))
      (node (ref "U4") (pin "4") (pinfunction "SDA_4") (pintype "bidirectional"))
    )
    (net (code "41") (name "/SDA_S4") (class "Default")
      (node (ref "SDA_S4_C1") (pin "TP") (pinfunction "TP_TP") (pintype "input"))
      (node (ref "U1") (pin "59") (pinfunction "P1.1_59") (pintype "bidirectional"))
    )
    (net (code "42") (name "/SDA_S4_U") (class "Default")
      (node (ref "SDA_S4_C4_C4") (pin "TP") (pinfunction "TP_TP") (pintype "input"))
      (node (ref "X1") (pin "8") (pinfunction "1_8") (pintype "passive"))
    )
    (net (code "43") (name "/SDA_S4_U_1") (class "Default")
      (node (ref "R24") (pin "1") (pinfunction "1_1") (pintype "passive"))
      (node (ref "U5") (pin "4") (pinfunction "SDA_4") (pintype "bidirectional"))
      (node (ref "X2") (pin "8") (pinfunction "1_8") (pintype "passive"))
    )
    (net (code "44") (name "/SWDCLK") (class "Default")
      (node (ref "R2") (pin "2") (pinfunction "2_2") (pintype "passive"))
      (node (ref "U1") (pin "21") (pinfunction "P3.3_21") (pintype "bidirectional"))
    )
    (net (code "45") (name "/SWDIO") (class "Default")
      (node (ref "R3") (pin "2") (pinfunction "2_2") (pintype "passive"))
      (node (ref "U1") (pin "20") (pinfunction "P3.2_20") (pintype "bidirectional"))
    )
    (net (code "46") (name "/UART_RX") (class "Default")
      (node (ref "U1") (pin "37") (pinfunction "P7.0/SCB3:SCL1_37") (pintype "bidirectional"))
    )
    (net (code "47") (name "/UART_TX") (class "Default")
      (node (ref "U1") (pin "38") (pinfunction "P7.1/SCB3:SDA1_38") (pintype "bidirectional"))
    )
    (net (code "48") (name "/VCCD") (class "Default")
      (node (ref "C7") (pin "1") (pinfunction "1_1") (pintype "passive"))
      (node (ref "U1") (pin "48") (pinfunction "VCCD_48") (pintype "bidirectional"))
    )
    (net (code "49") (name "/VCC_C2") (class "Default")
      (node (ref "DINA") (pin "2") (pinfunction "2_2") (pintype "passive"))
      (node (ref "IC1") (pin "3") (pinfunction "IN_3") (pintype "input"))
      (node (ref "VCC_1_C2") (pin "TP") (pinfunction "TP_TP") (pintype "input"))
      (node (ref "VCC_2_C2") (pin "TP") (pinfunction "TP_TP") (pintype "input"))
      (node (ref "VCC_C2") (pin "TP") (pinfunction "TP_TP") (pintype "input"))
      (node (ref "VCC_C2_C3") (pin "TP") (pinfunction "TP_TP") (pintype "input"))
    )
    (net (code "50") (name "/VCC_C3") (class "Default")
      (node (ref "VCC_1_C3") (pin "TP") (pinfunction "TP_TP") (pintype "input"))
      (node (ref "VCC_2_C3") (pin "TP") (pinfunction "TP_TP") (pintype "input"))
      (node (ref "VCC_3_C3") (pin "TP") (pinfunction "TP_TP") (pintype "input"))
      (node (ref "VCC_4_C3") (pin "TP") (pinfunction "TP_TP") (pintype "input"))
      (node (ref "VCC_C3") (pin "TP") (pinfunction "TP_TP") (pintype "input"))
      (node (ref "X1") (pin "1") (pinfunction "1_1") (pintype "passive"))
    )
    (net (code "51") (name "/VCC_C4") (class "Default")
      (node (ref "VCC_1_C4") (pin "TP") (pinfunction "TP_TP") (pintype "input"))
      (node (ref "VCC_2_C4") (pin "TP") (pinfunction "TP_TP") (pintype "input"))
      (node (ref "VCC_3_C4") (pin "TP") (pinfunction "TP_TP") (pintype "input"))
      (node (ref "VCC_4_C4") (pin "TP") (pinfunction "TP_TP") (pintype "input"))
      (node (ref "X2") (pin "1") (pinfunction "1_1") (pintype "passive"))
    )
    (net (code "52") (name "/VDDA") (class "Default")
      (node (ref "U1") (pin "11") (pinfunction "VDDA1_11") (pintype "bidirectional"))
      (node (ref "U1") (pin "56") (pinfunction "VDDA2_56") (pintype "bidirectional"))
      (node (ref "VDDA_C1") (pin "TP") (pinfunction "TP_TP") (pintype "input"))
    )
    (net (code "53") (name "/VDDA2") (class "Default")
      (node (ref "L1") (pin "2") (pinfunction "2_2") (pintype "passive"))
      (node (ref "VDDA_C2") (pin "TP") (pinfunction "TP_TP") (pintype "input"))
    )
    (net (code "54") (name "/VDDD") (class "Default")
      (node (ref "U1") (pin "50") (pinfunction "VDDD_50") (pintype "bidirectional"))
      (node (ref "VDDD_C1") (pin "TP") (pinfunction "TP_TP") (pintype "input"))
    )
    (net (code "55") (name "/VDDD2") (class "Default")
      (node (ref "L2") (pin "2") (pinfunction "2_2") (pintype "passive"))
      (node (ref "VDDD_C2") (pin "TP") (pinfunction "TP_TP") (pintype "input"))
    )
    (net (code "56") (name "/VDDIO") (class "Default")
      (node (ref "U1") (pin "26") (pinfunction "VDDIO_26") (pintype "bidirectional"))
      (node (ref "VDDIO_C1") (pin "TP") (pinfunction "TP_TP") (pintype "input"))
    )
    (net (code "57") (name "/VDDIO2") (class "Default")
      (node (ref "R15") (pin "2") (pinfunction "2_2") (pintype "passive"))
      (node (ref "VDDIO_C2") (pin "TP") (pinfunction "TP_TP") (pintype "input"))
    )
    (net (code "58") (name "/XRES") (class "Default")
      (node (ref "C10") (pin "1") (pinfunction "1_1") (pintype "passive"))
      (node (ref "R1") (pin "2") (pinfunction "2_2") (pintype "passive"))
      (node (ref "R14") (pin "2") (pinfunction "2_2") (pintype "passive"))
      (node (ref "U1") (pin "47") (pinfunction "XRES_47") (pintype "bidirectional"))
    )
    (net (code "59") (name "GND1") (class "Default")
      (node (ref "C10") (pin "2") (pinfunction "2_2") (pintype "passive"))
      (node (ref "C4") (pin "2") (pinfunction "2_2") (pintype "passive"))
      (node (ref "C5") (pin "2") (pinfunction "2_2") (pintype "passive"))
      (node (ref "C6") (pin "2") (pinfunction "2_2") (pintype "passive"))
      (node (ref "C7") (pin "2") (pinfunction "2_2") (pintype "passive"))
      (node (ref "C8") (pin "2") (pinfunction "2_2") (pintype "passive"))
      (node (ref "C9") (pin "2") (pinfunction "2_2") (pintype "passive"))
      (node (ref "CN1") (pin "D-") (pinfunction "D-_D-") (pintype "bidirectional"))
      (node (ref "GND_1_C1") (pin "TP") (pinfunction "TP_TP") (pintype "input"))
      (node (ref "GND_2_C1") (pin "TP") (pinfunction "TP_TP") (pintype "input"))
      (node (ref "GND_3_C1") (pin "TP") (pinfunction "TP_TP") (pintype "input"))
      (node (ref "GND_4_C1") (pin "TP") (pinfunction "TP_TP") (pintype "input"))
      (node (ref "GND_C1") (pin "TP") (pinfunction "TP_TP") (pintype "input"))
      (node (ref "R13") (pin "1") (pinfunction "1_1") (pintype "passive"))
      (node (ref "R17") (pin "2") (pinfunction "2_2") (pintype "passive"))
      (node (ref "R18") (pin "1") (pinfunction "1_1") (pintype "passive"))
      (node (ref "R19") (pin "2") (pinfunction "2_2") (pintype "passive"))
      (node (ref "R4") (pin "2") (pinfunction "2_2") (pintype "passive"))
      (node (ref "U$1") (pin "2") (pinfunction "GND_2") (pintype "power_in"))
      (node (ref "U1") (pin "10") (pinfunction "VSSA1_10") (pintype "bidirectional"))
      (node (ref "U1") (pin "17") (pinfunction "VSSIO_17") (pintype "bidirectional"))
      (node (ref "U1") (pin "49") (pinfunction "VSSD_49") (pintype "bidirectional"))
      (node (ref "U1") (pin "57") (pinfunction "VSSA2_57") (pintype "bidirectional"))
      (node (ref "U2") (pin "12") (pinfunction "GND_12") (pintype "power_in"))
      (node (ref "U2") (pin "13") (pinfunction "GND_13") (pintype "power_in"))
    )
    (net (code "60") (name "GND2") (class "Default")
      (node (ref "DINA") (pin "3") (pinfunction "3_3") (pintype "passive"))
      (node (ref "GND_1_C2") (pin "TP") (pinfunction "TP_TP") (pintype "input"))
      (node (ref "GND_2_C2") (pin "TP") (pinfunction "TP_TP") (pintype "input"))
      (node (ref "GND_C2") (pin "TP") (pinfunction "TP_TP") (pintype "input"))
      (node (ref "GND_C2_C3") (pin "TP") (pinfunction "TP_TP") (pintype "input"))
      (node (ref "IC1") (pin "1") (pinfunction "ADJ_1") (pintype "input"))
      (node (ref "R20") (pin "2") (pinfunction "2_2") (pintype "passive"))
      (node (ref "R23") (pin "2") (pinfunction "2_2") (pintype "passive"))
      (node (ref "R5") (pin "1") (pinfunction "1_1") (pintype "passive"))
      (node (ref "U3") (pin "12") (pinfunction "GND_12") (pintype "power_in"))
      (node (ref "U3") (pin "13") (pinfunction "GND_13") (pintype "power_in"))
    )
    (net (code "61") (name "GND3") (class "Default")
      (node (ref "GND_1_C3") (pin "TP") (pinfunction "TP_TP") (pintype "input"))
      (node (ref "GND_2_C3") (pin "TP") (pinfunction "TP_TP") (pintype "input"))
      (node (ref "GND_3_C3") (pin "TP") (pinfunction "TP_TP") (pintype "input"))
      (node (ref "GND_4_C3") (pin "TP") (pinfunction "TP_TP") (pintype "input"))
      (node (ref "GND_C3") (pin "TP") (pinfunction "TP_TP") (pintype "input"))
      (node (ref "R21") (pin "2") (pinfunction "2_2") (pintype "passive"))
      (node (ref "R7") (pin "1") (pinfunction "1_1") (pintype "passive"))
      (node (ref "U4") (pin "12") (pinfunction "GND_12") (pintype "power_in"))
      (node (ref "U4") (pin "13") (pinfunction "GND_13") (pintype "power_in"))
      (node (ref "X1") (pin "2") (pinfunction "1_2") (pintype "passive"))
      (node (ref "X1") (pin "6") (pinfunction "1_6") (pintype "passive"))
    )
    (net (code "62") (name "GND4") (class "Default")
      (node (ref "GND_1_C4") (pin "TP") (pinfunction "TP_TP") (pintype "input"))
      (node (ref "GND_2_C4") (pin "TP") (pinfunction "TP_TP") (pintype "input"))
      (node (ref "GND_3_C4") (pin "TP") (pinfunction "TP_TP") (pintype "input"))
      (node (ref "GND_4_C4") (pin "TP") (pinfunction "TP_TP") (pintype "input"))
      (node (ref "R22") (pin "2") (pinfunction "2_2") (pintype "passive"))
      (node (ref "R9") (pin "1") (pinfunction "1_1") (pintype "passive"))
      (node (ref "U5") (pin "12") (pinfunction "GND_12") (pintype "power_in"))
      (node (ref "U5") (pin "13") (pinfunction "GND_13") (pintype "power_in"))
      (node (ref "X2") (pin "2") (pinfunction "1_2") (pintype "passive"))
      (node (ref "X2") (pin "6") (pinfunction "1_6") (pintype "passive"))
    )
    (net (code "63") (name "Net-(CANH_1_C2-PadTP)") (class "Default")
      (node (ref "CANH_1_C2") (pin "TP") (pinfunction "TP_TP") (pintype "input"))
      (node (ref "CANH_2_C2") (pin "TP") (pinfunction "TP_TP") (pintype "input"))
      (node (ref "CANH_C2") (pin "TP") (pinfunction "TP_TP") (pintype "input"))
      (node (ref "CANH_C2_C3") (pin "TP") (pinfunction "TP_TP") (pintype "input"))
    )
    (net (code "64") (name "Net-(CANL_1_C2-PadTP)") (class "Default")
      (node (ref "CANL_1_C2") (pin "TP") (pinfunction "TP_TP") (pintype "input"))
      (node (ref "CANL_2_C2") (pin "TP") (pinfunction "TP_TP") (pintype "input"))
      (node (ref "CANL_C2") (pin "TP") (pinfunction "TP_TP") (pintype "input"))
      (node (ref "CANL_C2_C3") (pin "TP") (pinfunction "TP_TP") (pintype "input"))
    )
    (net (code "65") (name "Net-(CN1-PadD+)") (class "Default")
      (node (ref "CN1") (pin "D+") (pinfunction "D+_D+") (pintype "bidirectional"))
      (node (ref "R1") (pin "1") (pinfunction "1_1") (pintype "passive"))
    )
    (net (code "66") (name "Net-(CN1-PadGND)") (class "Default")
      (node (ref "CN1") (pin "GND") (pinfunction "GND_GND") (pintype "power_in"))
      (node (ref "R3") (pin "1") (pinfunction "1_1") (pintype "passive"))
    )
    (net (code "67") (name "Net-(CN1-PadID)") (class "Default")
      (node (ref "CN1") (pin "ID") (pinfunction "ID_ID") (pintype "bidirectional"))
      (node (ref "R2") (pin "1") (pinfunction "1_1") (pintype "passive"))
    )
    (net (code "68") (name "Net-(DINA-Pad1)") (class "Default")
      (node (ref "DINA") (pin "1") (pinfunction "1_1") (pintype "passive"))
      (node (ref "DN_C2") (pin "TP") (pinfunction "TP_TP") (pintype "input"))
    )
    (net (code "69") (name "Net-(DN_C1-PadTP)") (class "Default")
      (node (ref "DN_C1") (pin "TP") (pinfunction "TP_TP") (pintype "input"))
      (node (ref "S1") (pin "2") (pinfunction "2_2") (pintype "passive"))
    )
    (net (code "70") (name "Net-(LED1-PadC)") (class "Default")
      (node (ref "LED1") (pin "C") (pinfunction "C_C") (pintype "passive"))
      (node (ref "R19") (pin "1") (pinfunction "1_1") (pintype "passive"))
    )
    (net (code "71") (name "Net-(LED2-PadC)") (class "Default")
      (node (ref "LED2") (pin "C") (pinfunction "C_C") (pintype "passive"))
      (node (ref "R20") (pin "1") (pinfunction "1_1") (pintype "passive"))
    )
    (net (code "72") (name "Net-(LED3-PadC)") (class "Default")
      (node (ref "LED3") (pin "C") (pinfunction "C_C") (pintype "passive"))
      (node (ref "R21") (pin "1") (pinfunction "1_1") (pintype "passive"))
    )
    (net (code "73") (name "Net-(LED4-PadC)") (class "Default")
      (node (ref "LED4") (pin "C") (pinfunction "C_C") (pintype "passive"))
      (node (ref "R22") (pin "1") (pinfunction "1_1") (pintype "passive"))
    )
    (net (code "74") (name "Net-(LED5-PadC)") (class "Default")
      (node (ref "LED5") (pin "C") (pinfunction "C_C") (pintype "passive"))
      (node (ref "R23") (pin "1") (pinfunction "1_1") (pintype "passive"))
    )
    (net (code "75") (name "Net-(L_C1_C3-PadTP)") (class "Default")
      (node (ref "L_C1_C3") (pin "TP") (pinfunction "TP_TP") (pintype "input"))
      (node (ref "L_C3_C2") (pin "TP") (pinfunction "TP_TP") (pintype "input"))
    )
    (net (code "76") (name "Net-(L_C1_C4-PadTP)") (class "Default")
      (node (ref "L_C1_C4") (pin "TP") (pinfunction "TP_TP") (pintype "input"))
      (node (ref "L_C4_C1") (pin "TP") (pinfunction "TP_TP") (pintype "input"))
    )
    (net (code "77") (name "Net-(R4-Pad1)") (class "Default")
      (node (ref "R4") (pin "1") (pinfunction "1_1") (pintype "passive"))
      (node (ref "U2") (pin "2") (pinfunction "IR_CA_2") (pintype "power_in"))
      (node (ref "U2") (pin "3") (pinfunction "IR_CA_3") (pintype "power_in"))
    )
    (net (code "78") (name "Net-(R5-Pad2)") (class "Default")
      (node (ref "R5") (pin "2") (pinfunction "2_2") (pintype "passive"))
      (node (ref "U3") (pin "2") (pinfunction "IR_CA_2") (pintype "power_in"))
      (node (ref "U3") (pin "3") (pinfunction "IR_CA_3") (pintype "power_in"))
    )
    (net (code "79") (name "Net-(R7-Pad2)") (class "Default")
      (node (ref "R7") (pin "2") (pinfunction "2_2") (pintype "passive"))
      (node (ref "U4") (pin "2") (pinfunction "IR_CA_2") (pintype "power_in"))
      (node (ref "U4") (pin "3") (pinfunction "IR_CA_3") (pintype "power_in"))
    )
    (net (code "80") (name "Net-(R9-Pad2)") (class "Default")
      (node (ref "R9") (pin "2") (pinfunction "2_2") (pintype "passive"))
      (node (ref "U5") (pin "2") (pinfunction "IR_CA_2") (pintype "power_in"))
      (node (ref "U5") (pin "3") (pinfunction "IR_CA_3") (pintype "power_in"))
    )
    (net (code "81") (name "Net-(R11-Pad2)") (class "Default")
      (node (ref "R11") (pin "2") (pinfunction "2_2") (pintype "passive"))
      (node (ref "R13") (pin "2") (pinfunction "2_2") (pintype "passive"))
    )
    (net (code "82") (name "Net-(SCL_S3_C1_C3-PadTP)") (class "Default")
      (node (ref "SCL_S3_C1_C3") (pin "TP") (pinfunction "TP_TP") (pintype "input"))
      (node (ref "SCL_S3_C3_C1") (pin "TP") (pinfunction "TP_TP") (pintype "input"))
    )
    (net (code "83") (name "Net-(SCL_S4_C1_C4-PadTP)") (class "Default")
      (node (ref "SCL_S4_C1_C4") (pin "TP") (pinfunction "TP_TP") (pintype "input"))
      (node (ref "SCL_S4_C4_C1") (pin "TP") (pinfunction "TP_TP") (pintype "input"))
    )
    (net (code "84") (name "Net-(SDA_S3_C1_C1-PadTP)") (class "Default")
      (node (ref "SDA_S3_C1_C1") (pin "TP") (pinfunction "TP_TP") (pintype "input"))
      (node (ref "SDA_S3_C3_C3") (pin "TP") (pinfunction "TP_TP") (pintype "input"))
    )
    (net (code "85") (name "Net-(SDA_S4_C1_C1-PadTP)") (class "Default")
      (node (ref "SDA_S4_C1_C1") (pin "TP") (pinfunction "TP_TP") (pintype "input"))
      (node (ref "SDA_S4_C4_C3") (pin "TP") (pinfunction "TP_TP") (pintype "input"))
    )
    (net (code "86") (name "Net-(U$1-CANH)") (class "Default")
      (node (ref "R16") (pin "2") (pinfunction "2_2") (pintype "passive"))
      (node (ref "S1") (pin "4") (pinfunction "4_4") (pintype "passive"))
      (node (ref "U$1") (pin "7") (pinfunction "CANH_7") (pintype "bidirectional"))
    )
    (net (code "87") (name "Net-(U$1-RS)") (class "Default")
      (node (ref "R17") (pin "1") (pinfunction "1_1") (pintype "passive"))
      (node (ref "U$1") (pin "8") (pinfunction "RS_8") (pintype "bidirectional"))
    )
    (net (code "88") (name "Net-(VCC_1_C1-PadTP)") (class "Default")
      (node (ref "VCC_1_C1") (pin "TP") (pinfunction "TP_TP") (pintype "input"))
      (node (ref "VCC_2_C1") (pin "TP") (pinfunction "TP_TP") (pintype "input"))
      (node (ref "VCC_3_C1") (pin "TP") (pinfunction "TP_TP") (pintype "input"))
      (node (ref "VCC_4_C1") (pin "TP") (pinfunction "TP_TP") (pintype "input"))
      (node (ref "VCC_C1") (pin "TP") (pinfunction "TP_TP") (pintype "input"))
    )
    (net (code "89") (name "unconnected-(MECH_LINK_1-PadTP)") (class "Default")
      (node (ref "MECH_LINK_1") (pin "TP") (pinfunction "TP_TP") (pintype "input"))
    )
    (net (code "90") (name "unconnected-(MECH_LINK_2-PadTP)") (class "Default")
      (node (ref "MECH_LINK_2") (pin "TP") (pinfunction "TP_TP") (pintype "input"))
    )
    (net (code "91") (name "unconnected-(MECH_LINK_3-PadTP)") (class "Default")
      (node (ref "MECH_LINK_3") (pin "TP") (pinfunction "TP_TP") (pintype "input"))
    )
    (net (code "92") (name "unconnected-(MECH_LINK_4-PadTP)") (class "Default")
      (node (ref "MECH_LINK_4") (pin "TP") (pinfunction "TP_TP") (pintype "input"))
    )
    (net (code "93") (name "unconnected-(MECH_LINK_5-PadTP)") (class "Default")
      (node (ref "MECH_LINK_5") (pin "TP") (pinfunction "TP_TP") (pintype "input"))
    )
    (net (code "94") (name "unconnected-(MECH_LINK_6-PadTP)") (class "Default")
      (node (ref "MECH_LINK_6") (pin "TP") (pinfunction "TP_TP") (pintype "input"))
    )
    (net (code "95") (name "unconnected-(MECH_LINK_7-PadTP)") (class "Default")
      (node (ref "MECH_LINK_7") (pin "TP") (pinfunction "TP_TP") (pintype "input"))
    )
    (net (code "96") (name "unconnected-(MECH_LINK_8-PadTP)") (class "Default")
      (node (ref "MECH_LINK_8") (pin "TP") (pinfunction "TP_TP") (pintype "input"))
    )
    (net (code "97") (name "unconnected-(MECH_LINK_9-PadTP)") (class "Default")
      (node (ref "MECH_LINK_9") (pin "TP") (pinfunction "TP_TP") (pintype "input"))
    )
    (net (code "98") (name "unconnected-(MECH_LINK_11-PadTP)") (class "Default")
      (node (ref "MECH_LINK_11") (pin "TP") (pinfunction "TP_TP") (pintype "input"))
    )
    (net (code "99") (name "unconnected-(U$1-VREF-Pad5)") (class "Default")
      (node (ref "U$1") (pin "5") (pinfunction "VREF_5") (pintype "bidirectional"))
    )
    (net (code "100") (name "unconnected-(U1-NC1-Pad34)") (class "Default")
      (node (ref "U1") (pin "34") (pinfunction "NC1_34") (pintype "bidirectional"))
    )
    (net (code "101") (name "unconnected-(U1-NC2-Pad35)") (class "Default")
      (node (ref "U1") (pin "35") (pinfunction "NC2_35") (pintype "bidirectional"))
    )
    (net (code "102") (name "unconnected-(U1-NC3-Pad36)") (class "Default")
      (node (ref "U1") (pin "36") (pinfunction "NC3_36") (pintype "bidirectional"))
    )
    (net (code "103") (name "unconnected-(U1-P0.0{slash}CAN1RX-Pad39)") (class "Default")
      (node (ref "U1") (pin "39") (pinfunction "P0.0/CAN1RX_39") (pintype "bidirectional"))
    )
    (net (code "104") (name "unconnected-(U1-P0.2-Pad41)") (class "Default")
      (node (ref "U1") (pin "41") (pinfunction "P0.2_41") (pintype "bidirectional"))
    )
    (net (code "105") (name "unconnected-(U1-P0.3-Pad42)") (class "Default")
      (node (ref "U1") (pin "42") (pinfunction "P0.3_42") (pintype "bidirectional"))
    )
    (net (code "106") (name "unconnected-(U1-P0.6-Pad45)") (class "Default")
      (node (ref "U1") (pin "45") (pinfunction "P0.6_45") (pintype "bidirectional"))
    )
    (net (code "107") (name "unconnected-(U1-P0.7{slash}CAN1TX_EN-Pad46)") (class "Default")
      (node (ref "U1") (pin "46") (pinfunction "P0.7/CAN1TX_EN_46") (pintype "bidirectional"))
    )
    (net (code "108") (name "unconnected-(U1-P1.2-Pad60)") (class "Default")
      (node (ref "U1") (pin "60") (pinfunction "P1.2_60") (pintype "bidirectional"))
    )
    (net (code "109") (name "unconnected-(U1-P1.3-Pad61)") (class "Default")
      (node (ref "U1") (pin "61") (pinfunction "P1.3_61") (pintype "bidirectional"))
    )
    (net (code "110") (name "unconnected-(U1-P1.4-Pad62)") (class "Default")
      (node (ref "U1") (pin "62") (pinfunction "P1.4_62") (pintype "bidirectional"))
    )
    (net (code "111") (name "unconnected-(U1-P1.5-Pad63)") (class "Default")
      (node (ref "U1") (pin "63") (pinfunction "P1.5_63") (pintype "bidirectional"))
    )
    (net (code "112") (name "unconnected-(U1-P1.6-Pad64)") (class "Default")
      (node (ref "U1") (pin "64") (pinfunction "P1.6_64") (pintype "bidirectional"))
    )
    (net (code "113") (name "unconnected-(U1-P3.0{slash}SCB1:RX-Pad18)") (class "Default")
      (node (ref "U1") (pin "18") (pinfunction "P3.0/SCB1:RX_18") (pintype "bidirectional"))
    )
    (net (code "114") (name "unconnected-(U1-P3.1{slash}SCB1:TX-Pad19)") (class "Default")
      (node (ref "U1") (pin "19") (pinfunction "P3.1/SCB1:TX_19") (pintype "bidirectional"))
    )
    (net (code "115") (name "unconnected-(U1-P3.4-Pad22)") (class "Default")
      (node (ref "U1") (pin "22") (pinfunction "P3.4_22") (pintype "bidirectional"))
    )
    (net (code "116") (name "unconnected-(U1-P3.5-Pad23)") (class "Default")
      (node (ref "U1") (pin "23") (pinfunction "P3.5_23") (pintype "bidirectional"))
    )
    (net (code "117") (name "unconnected-(U1-P3.6-Pad24)") (class "Default")
      (node (ref "U1") (pin "24") (pinfunction "P3.6_24") (pintype "bidirectional"))
    )
    (net (code "118") (name "unconnected-(U1-P3.7-Pad25)") (class "Default")
      (node (ref "U1") (pin "25") (pinfunction "P3.7_25") (pintype "bidirectional"))
    )
    (net (code "119") (name "unconnected-(U1-P4.4-Pad31)") (class "Default")
      (node (ref "U1") (pin "31") (pinfunction "P4.4_31") (pintype "bidirectional"))
    )
    (net (code "120") (name "unconnected-(U1-P4.5-Pad32)") (class "Default")
      (node (ref "U1") (pin "32") (pinfunction "P4.5_32") (pintype "bidirectional"))
    )
    (net (code "121") (name "unconnected-(U1-P4.6-Pad33)") (class "Default")
      (node (ref "U1") (pin "33") (pinfunction "P4.6_33") (pintype "bidirectional"))
    )
    (net (code "122") (name "unconnected-(U1-P5.2-Pad53)") (class "Default")
      (node (ref "U1") (pin "53") (pinfunction "P5.2_53") (pintype "bidirectional"))
    )
    (net (code "123") (name "unconnected-(U1-P5.3-Pad54)") (class "Default")
      (node (ref "U1") (pin "54") (pinfunction "P5.3_54") (pintype "bidirectional"))
    )
    (net (code "124") (name "unconnected-(U1-P5.5-Pad55)") (class "Default")
      (node (ref "U1") (pin "55") (pinfunction "P5.5_55") (pintype "bidirectional"))
    )
    (net (code "125") (name "unconnected-(U1-P6.2{slash}CAN0TX-Pad14)") (class "Default")
      (node (ref "U1") (pin "14") (pinfunction "P6.2/CAN0TX_14") (pintype "bidirectional"))
    )
    (net (code "126") (name "unconnected-(U1-P6.4-Pad15)") (class "Default")
      (node (ref "U1") (pin "15") (pinfunction "P6.4_15") (pintype "bidirectional"))
    )
    (net (code "127") (name "unconnected-(U1-P6.5-Pad16)") (class "Default")
      (node (ref "U1") (pin "16") (pinfunction "P6.5_16") (pintype "bidirectional"))
    )
    (net (code "128") (name "unconnected-(U2-INT-Pad6)") (class "Default")
      (node (ref "U2") (pin "6") (pinfunction "INT_6") (pintype "output"))
    )
    (net (code "129") (name "unconnected-(U3-INT-Pad6)") (class "Default")
      (node (ref "U3") (pin "6") (pinfunction "INT_6") (pintype "output"))
    )
    (net (code "130") (name "unconnected-(U4-INT-Pad6)") (class "Default")
      (node (ref "U4") (pin "6") (pinfunction "INT_6") (pintype "output"))
    )
    (net (code "131") (name "unconnected-(U5-INT-Pad6)") (class "Default")
      (node (ref "U5") (pin "6") (pinfunction "INT_6") (pintype "output"))
    )
    (net (code "132") (name "unconnected-(X1B-1-Pad10)") (class "Default")
      (node (ref "X1") (pin "10") (pinfunction "1_10") (pintype "passive"))
    )
    (net (code "133") (name "unconnected-(X2B-1-Pad10)") (class "Default")
      (node (ref "X2") (pin "10") (pinfunction "1_10") (pintype "passive"))
    )
  )
)
